# 4_waffling60-MXHS-ANSI_periferals.net
KiCad netlist of a schematic drawn in Altium Designer
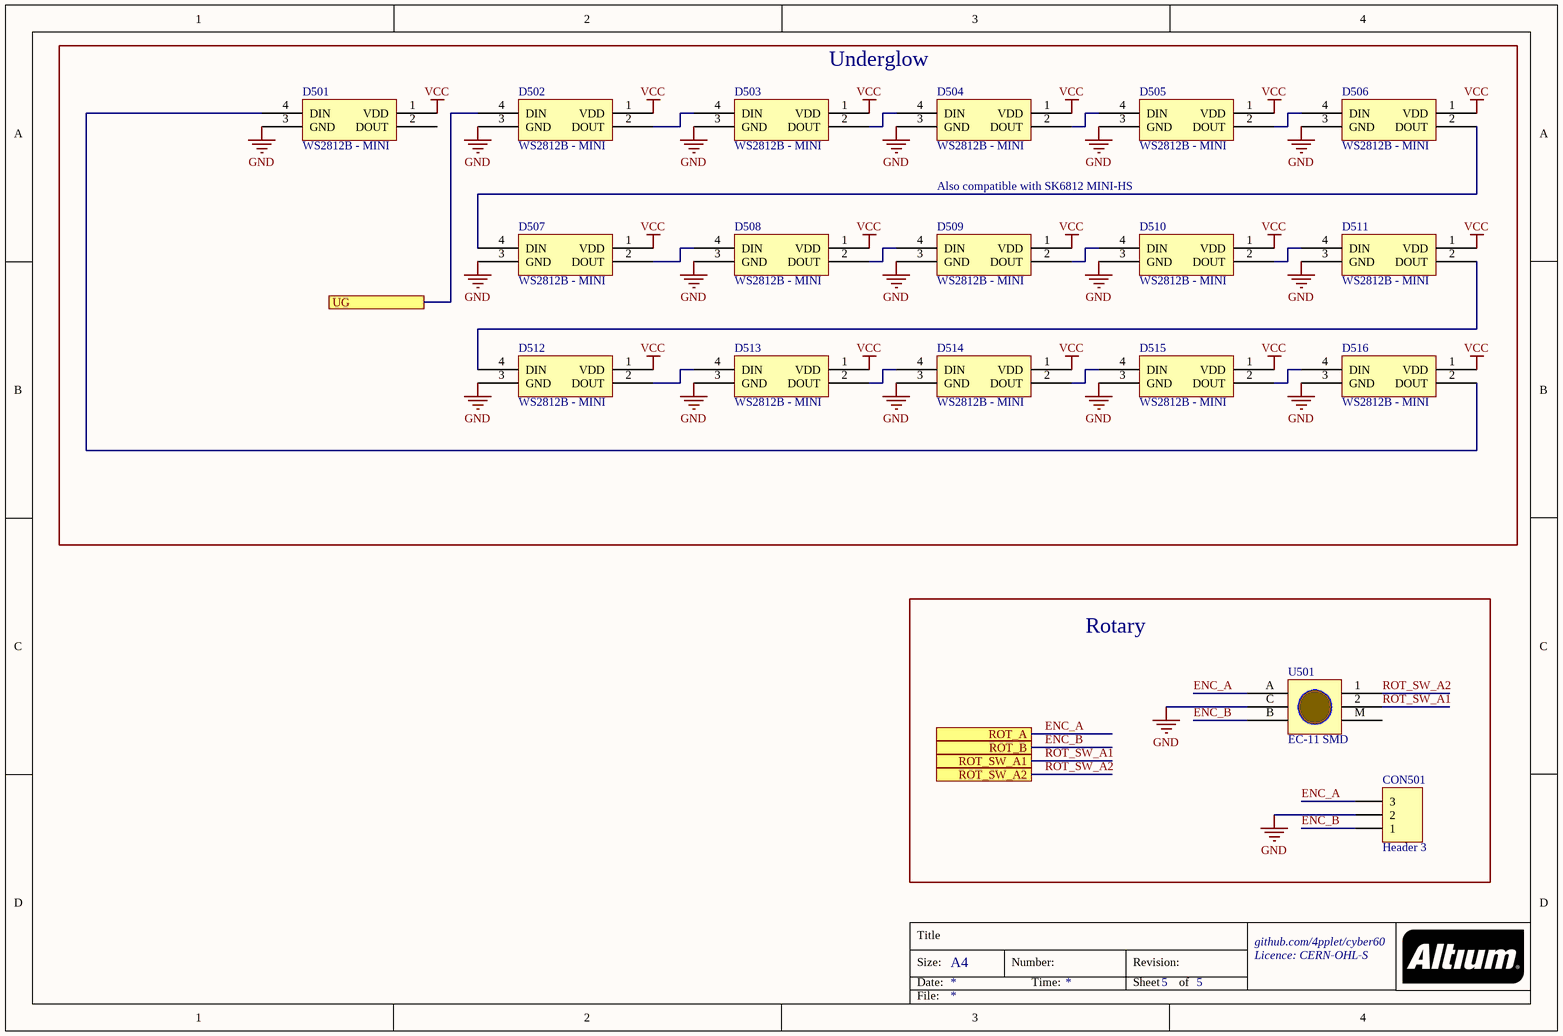
[diagram p0: 4_waffling60-MXHS-ANSI_periferals.SchDoc]

(export (version "E")
  (design (tool "Eeschema 10.0.6"))
  (components
    (comp (ref "CON501")
      (value "Header 3")
      (footprint "HDR1X3")
      (description "Header, 3-Pin")
      (libsource (lib "Miscellaneous Connectors") (part "Header 3"))
    )
    (comp (ref "D501")
      (value "WS2812B - MINI")
      (footprint "WS2812B - 2020")
      (fields (field (name "LCSC PART #") "C965555") (field (name "MRF.PART") "WS2812B-2020"))
      (libsource (lib "Keebs") (part "WS2812B"))
    )
    (comp (ref "D502")
      (value "WS2812B - MINI")
      (footprint "WS2812B - 2020")
      (fields (field (name "LCSC PART #") "C965555") (field (name "MRF.PART") "WS2812B-2020"))
      (libsource (lib "Keebs") (part "WS2812B"))
    )
    (comp (ref "D503")
      (value "WS2812B - MINI")
      (footprint "WS2812B - 2020")
      (fields (field (name "LCSC PART #") "C965555") (field (name "MRF.PART") "WS2812B-2020"))
      (libsource (lib "Keebs") (part "WS2812B"))
    )
    (comp (ref "D504")
      (value "WS2812B - MINI")
      (footprint "WS2812B - 2020")
      (fields (field (name "LCSC PART #") "C965555") (field (name "MRF.PART") "WS2812B-2020"))
      (libsource (lib "Keebs") (part "WS2812B"))
    )
    (comp (ref "D505")
      (value "WS2812B - MINI")
      (footprint "WS2812B - 2020")
      (fields (field (name "LCSC PART #") "C965555") (field (name "MRF.PART") "WS2812B-2020"))
      (libsource (lib "Keebs") (part "WS2812B"))
    )
    (comp (ref "D506")
      (value "WS2812B - MINI")
      (footprint "WS2812B - 2020")
      (fields (field (name "LCSC PART #") "C965555") (field (name "MRF.PART") "WS2812B-2020"))
      (libsource (lib "Keebs") (part "WS2812B"))
    )
    (comp (ref "D507")
      (value "WS2812B - MINI")
      (footprint "WS2812B - 2020")
      (fields (field (name "LCSC PART #") "C965555") (field (name "MRF.PART") "WS2812B-2020"))
      (libsource (lib "Keebs") (part "WS2812B"))
    )
    (comp (ref "D508")
      (value "WS2812B - MINI")
      (footprint "WS2812B - 2020")
      (fields (field (name "LCSC PART #") "C965555") (field (name "MRF.PART") "WS2812B-2020"))
      (libsource (lib "Keebs") (part "WS2812B"))
    )
    (comp (ref "D509")
      (value "WS2812B - MINI")
      (footprint "WS2812B - 2020")
      (fields (field (name "LCSC PART #") "C965555") (field (name "MRF.PART") "WS2812B-2020"))
      (libsource (lib "Keebs") (part "WS2812B"))
    )
    (comp (ref "D510")
      (value "WS2812B - MINI")
      (footprint "WS2812B - 2020")
      (fields (field (name "LCSC PART #") "C965555") (field (name "MRF.PART") "WS2812B-2020"))
      (libsource (lib "Keebs") (part "WS2812B"))
    )
    (comp (ref "D511")
      (value "WS2812B - MINI")
      (footprint "WS2812B - 2020")
      (fields (field (name "LCSC PART #") "C965555") (field (name "MRF.PART") "WS2812B-2020"))
      (libsource (lib "Keebs") (part "WS2812B"))
    )
    (comp (ref "D512")
      (value "WS2812B - MINI")
      (footprint "WS2812B - 2020")
      (fields (field (name "LCSC PART #") "C965555") (field (name "MRF.PART") "WS2812B-2020"))
      (libsource (lib "Keebs") (part "WS2812B"))
    )
    (comp (ref "D513")
      (value "WS2812B - MINI")
      (footprint "WS2812B - 2020")
      (fields (field (name "LCSC PART #") "C965555") (field (name "MRF.PART") "WS2812B-2020"))
      (libsource (lib "Keebs") (part "WS2812B"))
    )
    (comp (ref "D514")
      (value "WS2812B - MINI")
      (footprint "WS2812B - 2020")
      (fields (field (name "LCSC PART #") "C965555") (field (name "MRF.PART") "WS2812B-2020"))
      (libsource (lib "Keebs") (part "WS2812B"))
    )
    (comp (ref "D515")
      (value "WS2812B - MINI")
      (footprint "WS2812B - 2020")
      (fields (field (name "LCSC PART #") "C965555") (field (name "MRF.PART") "WS2812B-2020"))
      (libsource (lib "Keebs") (part "WS2812B"))
    )
    (comp (ref "D516")
      (value "WS2812B - MINI")
      (footprint "WS2812B - 2020")
      (fields (field (name "LCSC PART #") "C965555") (field (name "MRF.PART") "WS2812B-2020"))
      (libsource (lib "Keebs") (part "WS2812B"))
    )
    (comp (ref "U501") (value "EC-11 SMD") (footprint "EC11-SMD") (libsource (lib "Keebs") (part "EC-11")))
  )
  (nets
    (net (code "1") (name "/ENC_A") (class "Default")
      (node (ref "CON501") (pin "3") (pinfunction "3_3") (pintype "passive"))
      (node (ref "U501") (pin "A") (pinfunction "B_A") (pintype "passive"))
    )
    (net (code "2") (name "/ENC_B") (class "Default")
      (node (ref "CON501") (pin "1") (pinfunction "1_1") (pintype "passive"))
      (node (ref "U501") (pin "B") (pinfunction "B_B") (pintype "passive"))
    )
    (net (code "3") (name "/ROT_SW_A1") (class "Default")
      (node (ref "U501") (pin "2") (pinfunction "2_2") (pintype "passive"))
    )
    (net (code "4") (name "/ROT_SW_A2") (class "Default")
      (node (ref "U501") (pin "1") (pinfunction "1_1") (pintype "passive"))
    )
    (net (code "5") (name "/UG") (class "Default")
      (node (ref "D502") (pin "4") (pinfunction "DIN_4") (pintype "passive"))
    )
    (net (code "6") (name "GND") (class "Default")
      (node (ref "CON501") (pin "2") (pinfunction "2_2") (pintype "passive"))
      (node (ref "D501") (pin "3") (pinfunction "GND_3") (pintype "passive"))
      (node (ref "D502") (pin "3") (pinfunction "GND_3") (pintype "passive"))
      (node (ref "D503") (pin "3") (pinfunction "GND_3") (pintype "passive"))
      (node (ref "D504") (pin "3") (pinfunction "GND_3") (pintype "passive"))
      (node (ref "D505") (pin "3") (pinfunction "GND_3") (pintype "passive"))
      (node (ref "D506") (pin "3") (pinfunction "GND_3") (pintype "passive"))
      (node (ref "D507") (pin "3") (pinfunction "GND_3") (pintype "passive"))
      (node (ref "D508") (pin "3") (pinfunction "GND_3") (pintype "passive"))
      (node (ref "D509") (pin "3") (pinfunction "GND_3") (pintype "passive"))
      (node (ref "D510") (pin "3") (pinfunction "GND_3") (pintype "passive"))
      (node (ref "D511") (pin "3") (pinfunction "GND_3") (pintype "passive"))
      (node (ref "D512") (pin "3") (pinfunction "GND_3") (pintype "passive"))
      (node (ref "D513") (pin "3") (pinfunction "GND_3") (pintype "passive"))
      (node (ref "D514") (pin "3") (pinfunction "GND_3") (pintype "passive"))
      (node (ref "D515") (pin "3") (pinfunction "GND_3") (pintype "passive"))
      (node (ref "D516") (pin "3") (pinfunction "GND_3") (pintype "passive"))
      (node (ref "U501") (pin "C") (pinfunction "C_C") (pintype "passive"))
    )
    (net (code "7") (name "Net-(D501-DIN)") (class "Default")
      (node (ref "D501") (pin "4") (pinfunction "DIN_4") (pintype "passive"))
      (node (ref "D516") (pin "2") (pinfunction "DOUT_2") (pintype "passive"))
    )
    (net (code "8") (name "Net-(D502-DOUT)") (class "Default")
      (node (ref "D502") (pin "2") (pinfunction "DOUT_2") (pintype "passive"))
      (node (ref "D503") (pin "4") (pinfunction "DIN_4") (pintype "passive"))
    )
    (net (code "9") (name "Net-(D503-DOUT)") (class "Default")
      (node (ref "D503") (pin "2") (pinfunction "DOUT_2") (pintype "passive"))
      (node (ref "D504") (pin "4") (pinfunction "DIN_4") (pintype "passive"))
    )
    (net (code "10") (name "Net-(D504-DOUT)") (class "Default")
      (node (ref "D504") (pin "2") (pinfunction "DOUT_2") (pintype "passive"))
      (node (ref "D505") (pin "4") (pinfunction "DIN_4") (pintype "passive"))
    )
    (net (code "11") (name "Net-(D505-DOUT)") (class "Default")
      (node (ref "D505") (pin "2") (pinfunction "DOUT_2") (pintype "passive"))
      (node (ref "D506") (pin "4") (pinfunction "DIN_4") (pintype "passive"))
    )
    (net (code "12") (name "Net-(D506-DOUT)") (class "Default")
      (node (ref "D506") (pin "2") (pinfunction "DOUT_2") (pintype "passive"))
      (node (ref "D507") (pin "4") (pinfunction "DIN_4") (pintype "passive"))
    )
    (net (code "13") (name "Net-(D507-DOUT)") (class "Default")
      (node (ref "D507") (pin "2") (pinfunction "DOUT_2") (pintype "passive"))
      (node (ref "D508") (pin "4") (pinfunction "DIN_4") (pintype "passive"))
    )
    (net (code "14") (name "Net-(D508-DOUT)") (class "Default")
      (node (ref "D508") (pin "2") (pinfunction "DOUT_2") (pintype "passive"))
      (node (ref "D509") (pin "4") (pinfunction "DIN_4") (pintype "passive"))
    )
    (net (code "15") (name "Net-(D509-DOUT)") (class "Default")
      (node (ref "D509") (pin "2") (pinfunction "DOUT_2") (pintype "passive"))
      (node (ref "D510") (pin "4") (pinfunction "DIN_4") (pintype "passive"))
    )
    (net (code "16") (name "Net-(D510-DOUT)") (class "Default")
      (node (ref "D510") (pin "2") (pinfunction "DOUT_2") (pintype "passive"))
      (node (ref "D511") (pin "4") (pinfunction "DIN_4") (pintype "passive"))
    )
    (net (code "17") (name "Net-(D511-DOUT)") (class "Default")
      (node (ref "D511") (pin "2") (pinfunction "DOUT_2") (pintype "passive"))
      (node (ref "D512") (pin "4") (pinfunction "DIN_4") (pintype "passive"))
    )
    (net (code "18") (name "Net-(D512-DOUT)") (class "Default")
      (node (ref "D512") (pin "2") (pinfunction "DOUT_2") (pintype "passive"))
      (node (ref "D513") (pin "4") (pinfunction "DIN_4") (pintype "passive"))
    )
    (net (code "19") (name "Net-(D513-DOUT)") (class "Default")
      (node (ref "D513") (pin "2") (pinfunction "DOUT_2") (pintype "passive"))
      (node (ref "D514") (pin "4") (pinfunction "DIN_4") (pintype "passive"))
    )
    (net (code "20") (name "Net-(D514-DOUT)") (class "Default")
      (node (ref "D514") (pin "2") (pinfunction "DOUT_2") (pintype "passive"))
      (node (ref "D515") (pin "4") (pinfunction "DIN_4") (pintype "passive"))
    )
    (net (code "21") (name "Net-(D515-DOUT)") (class "Default")
      (node (ref "D515") (pin "2") (pinfunction "DOUT_2") (pintype "passive"))
      (node (ref "D516") (pin "4") (pinfunction "DIN_4") (pintype "passive"))
    )
    (net (code "22") (name "VCC") (class "Default")
      (node (ref "D501") (pin "1") (pinfunction "VDD_1") (pintype "passive"))
      (node (ref "D502") (pin "1") (pinfunction "VDD_1") (pintype "passive"))
      (node (ref "D503") (pin "1") (pinfunction "VDD_1") (pintype "passive"))
      (node (ref "D504") (pin "1") (pinfunction "VDD_1") (pintype "passive"))
      (node (ref "D505") (pin "1") (pinfunction "VDD_1") (pintype "passive"))
      (node (ref "D506") (pin "1") (pinfunction "VDD_1") (pintype "passive"))
      (node (ref "D507") (pin "1") (pinfunction "VDD_1") (pintype "passive"))
      (node (ref "D508") (pin "1") (pinfunction "VDD_1") (pintype "passive"))
      (node (ref "D509") (pin "1") (pinfunction "VDD_1") (pintype "passive"))
      (node (ref "D510") (pin "1") (pinfunction "VDD_1") (pintype "passive"))
      (node (ref "D511") (pin "1") (pinfunction "VDD_1") (pintype "passive"))
      (node (ref "D512") (pin "1") (pinfunction "VDD_1") (pintype "passive"))
      (node (ref "D513") (pin "1") (pinfunction "VDD_1") (pintype "passive"))
      (node (ref "D514") (pin "1") (pinfunction "VDD_1") (pintype "passive"))
      (node (ref "D515") (pin "1") (pinfunction "VDD_1") (pintype "passive"))
      (node (ref "D516") (pin "1") (pinfunction "VDD_1") (pintype "passive"))
    )
    (net (code "23") (name "unconnected-(D501-DOUT-Pad2)") (class "Default")
      (node (ref "D501") (pin "2") (pinfunction "DOUT_2") (pintype "passive"))
    )
    (net (code "24") (name "unconnected-(U501-PadM)") (class "Default")
      (node (ref "U501") (pin "M") (pinfunction "M_M") (pintype "passive"))
    )
  )
)
